# amplification.net
KiCad netlist of a schematic drawn in EAGLE
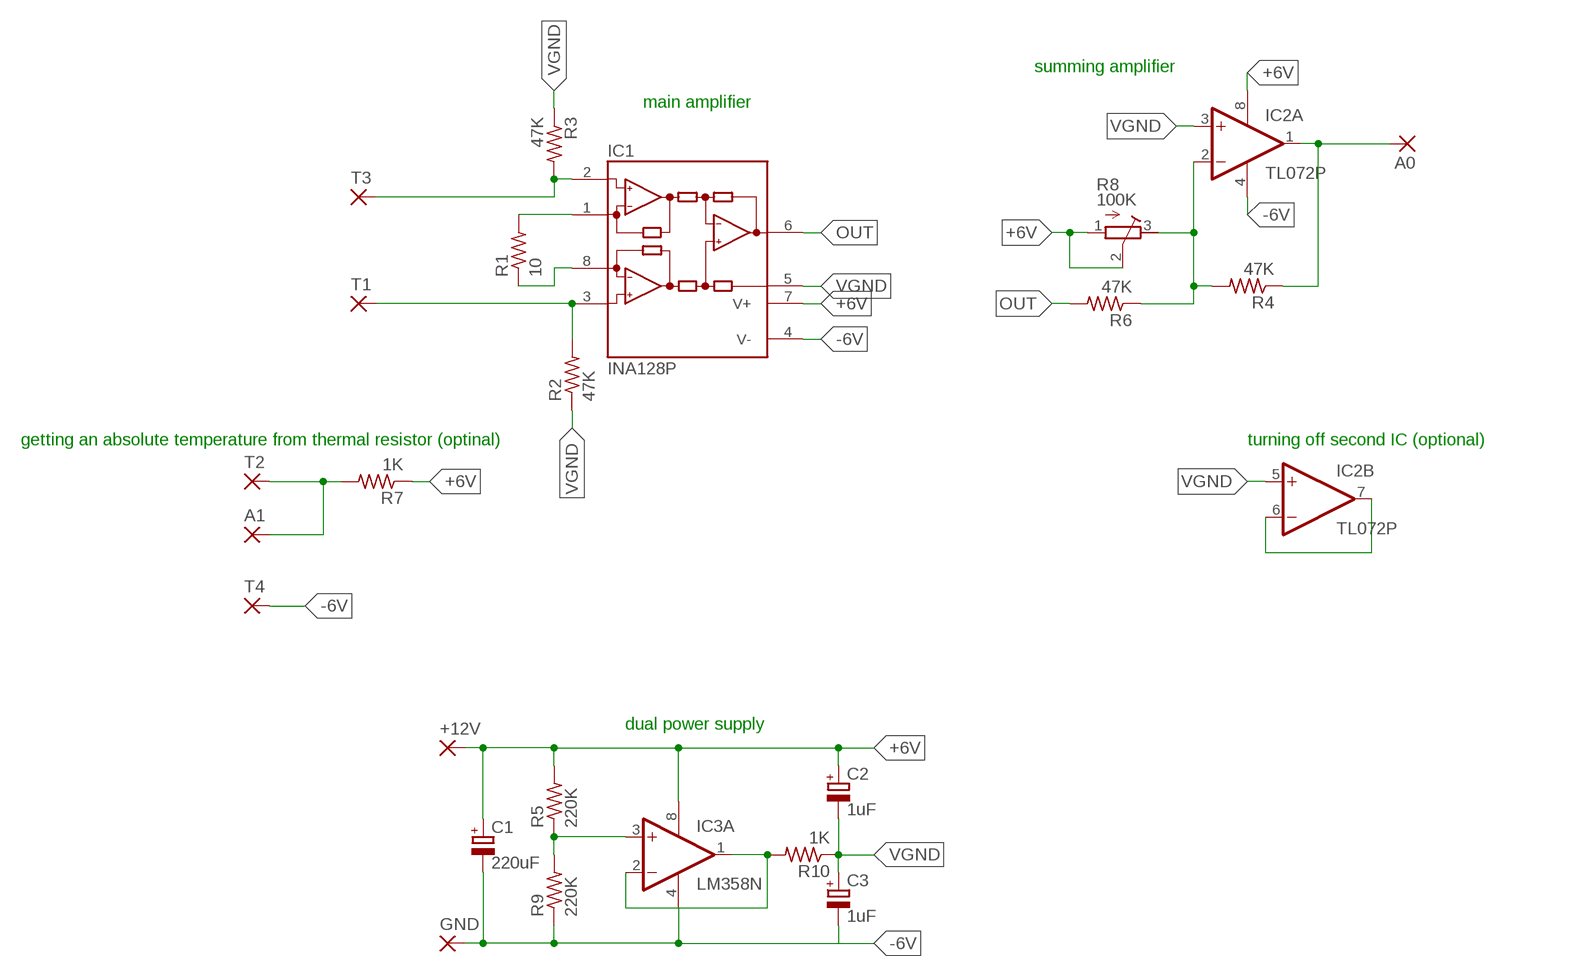
[diagram p0: schematic, sheet 1]

(export (version "E")
  (design (tool "Eeschema 10.0.6"))
  (components
    (comp (ref "+12V")
      (value "2,54/0,8")
      (footprint "eagle-import:2,54_0,8")
      (libsource (lib "eagle-import") (part "2,54/0,8"))
    )
    (comp (ref "A0")
      (value "2,54/0,8")
      (footprint "eagle-import:2,54_0,8")
      (libsource (lib "eagle-import") (part "2,54/0,8"))
    )
    (comp (ref "A1")
      (value "2,54/0,8")
      (footprint "eagle-import:2,54_0,8")
      (libsource (lib "eagle-import") (part "2,54/0,8"))
    )
    (comp (ref "C1")
      (value "220uF")
      (footprint "eagle-import:E2,5-6")
      (libsource (lib "eagle-import") (part "CPOL-EUE2.5-6"))
    )
    (comp (ref "C2")
      (value "1uF")
      (footprint "eagle-import:E2,5-6")
      (libsource (lib "eagle-import") (part "CPOL-EUE2.5-6"))
    )
    (comp (ref "C3")
      (value "1uF")
      (footprint "eagle-import:E2,5-6")
      (libsource (lib "eagle-import") (part "CPOL-EUE2.5-6"))
    )
    (comp (ref "GND")
      (value "2,54/0,8")
      (footprint "eagle-import:2,54_0,8")
      (libsource (lib "eagle-import") (part "2,54/0,8"))
    )
    (comp (ref "IC1")
      (value "INA128P")
      (footprint "eagle-import:DIL08")
      (fields (field (name "MF") "TEXAS INSTRUMENTS"))
      (libsource (lib "eagle-import") (part "INA128P"))
    )
    (comp (ref "IC2")
      (value "TL072P")
      (footprint "eagle-import:DIL08")
      (libsource (lib "eagle-import") (part "TL072P"))
    )
    (comp (ref "IC3")
      (value "LM358N")
      (footprint "eagle-import:DIL08")
      (libsource (lib "eagle-import") (part "LM358N"))
    )
    (comp (ref "R1")
      (value "10")
      (footprint "eagle-import:0207_10")
      (libsource (lib "eagle-import") (part "R-US_0207/10"))
    )
    (comp (ref "R2")
      (value "47K")
      (footprint "eagle-import:0207_10")
      (libsource (lib "eagle-import") (part "R-US_0207/10"))
    )
    (comp (ref "R3")
      (value "47K")
      (footprint "eagle-import:0207_10")
      (libsource (lib "eagle-import") (part "R-US_0207/10"))
    )
    (comp (ref "R4")
      (value "47K")
      (footprint "eagle-import:0207_10")
      (libsource (lib "eagle-import") (part "R-US_0207/10"))
    )
    (comp (ref "R5")
      (value "220K")
      (footprint "eagle-import:0207_10")
      (libsource (lib "eagle-import") (part "R-US_0207/10"))
    )
    (comp (ref "R6")
      (value "47K")
      (footprint "eagle-import:0207_10")
      (libsource (lib "eagle-import") (part "R-US_0207/10"))
    )
    (comp (ref "R7")
      (value "1K")
      (footprint "eagle-import:0207_10")
      (libsource (lib "eagle-import") (part "R-US_0207/10"))
    )
    (comp (ref "R8")
      (value "100K")
      (footprint "eagle-import:RTRIM64W")
      (libsource (lib "eagle-import") (part "R-TRIMM64W"))
    )
    (comp (ref "R9")
      (value "220K")
      (footprint "eagle-import:0207_10")
      (libsource (lib "eagle-import") (part "R-US_0207/10"))
    )
    (comp (ref "R10")
      (value "1K")
      (footprint "eagle-import:0207_10")
      (libsource (lib "eagle-import") (part "R-US_0207/10"))
    )
    (comp (ref "T1")
      (value "2,54/0,8")
      (footprint "eagle-import:2,54_0,8")
      (libsource (lib "eagle-import") (part "2,54/0,8"))
    )
    (comp (ref "T2")
      (value "2,54/0,8")
      (footprint "eagle-import:2,54_0,8")
      (libsource (lib "eagle-import") (part "2,54/0,8"))
    )
    (comp (ref "T3")
      (value "2,54/0,8")
      (footprint "eagle-import:2,54_0,8")
      (libsource (lib "eagle-import") (part "2,54/0,8"))
    )
    (comp (ref "T4")
      (value "2,54/0,8")
      (footprint "eagle-import:2,54_0,8")
      (libsource (lib "eagle-import") (part "2,54/0,8"))
    )
  )
  (nets
    (net (code "1") (name "+6V") (class "Default")
      (node (ref "+12V") (pin "1") (pinfunction "P_1") (pintype "passive"))
      (node (ref "C1") (pin "+") (pinfunction "+_+") (pintype "passive"))
      (node (ref "C2") (pin "+") (pinfunction "+_+") (pintype "passive"))
      (node (ref "IC1") (pin "7") (pinfunction "V+_7") (pintype "power_in"))
      (node (ref "IC2") (pin "8") (pinfunction "V+_8") (pintype "power_in"))
      (node (ref "IC3") (pin "8") (pinfunction "V+_8") (pintype "power_in"))
      (node (ref "R5") (pin "2") (pinfunction "2_2") (pintype "passive"))
      (node (ref "R7") (pin "1") (pinfunction "1_1") (pintype "passive"))
      (node (ref "R8") (pin "1") (pinfunction "A_1") (pintype "passive"))
      (node (ref "R8") (pin "2") (pinfunction "S_2") (pintype "passive"))
    )
    (net (code "2") (name "-6V") (class "Default")
      (node (ref "C1") (pin "-") (pinfunction "-_-") (pintype "passive"))
      (node (ref "C3") (pin "-") (pinfunction "-_-") (pintype "passive"))
      (node (ref "GND") (pin "1") (pinfunction "P_1") (pintype "passive"))
      (node (ref "IC1") (pin "4") (pinfunction "V-_4") (pintype "power_in"))
      (node (ref "IC2") (pin "4") (pinfunction "V-_4") (pintype "power_in"))
      (node (ref "IC3") (pin "4") (pinfunction "V-_4") (pintype "power_in"))
      (node (ref "R9") (pin "1") (pinfunction "1_1") (pintype "passive"))
      (node (ref "T4") (pin "1") (pinfunction "P_1") (pintype "passive"))
    )
    (net (code "3") (name "Net-(A0-P)") (class "Default")
      (node (ref "A0") (pin "1") (pinfunction "P_1") (pintype "passive"))
      (node (ref "IC2") (pin "1") (pinfunction "OUT_1") (pintype "output"))
      (node (ref "R4") (pin "1") (pinfunction "1_1") (pintype "passive"))
    )
    (net (code "4") (name "Net-(A1-P)") (class "Default")
      (node (ref "A1") (pin "1") (pinfunction "P_1") (pintype "passive"))
      (node (ref "R7") (pin "2") (pinfunction "2_2") (pintype "passive"))
      (node (ref "T2") (pin "1") (pinfunction "P_1") (pintype "passive"))
    )
    (net (code "5") (name "Net-(IC1-+IN)") (class "Default")
      (node (ref "IC1") (pin "3") (pinfunction "+IN_3") (pintype "input"))
      (node (ref "R2") (pin "2") (pinfunction "2_2") (pintype "passive"))
      (node (ref "T1") (pin "1") (pinfunction "P_1") (pintype "passive"))
    )
    (net (code "6") (name "Net-(IC1--IN)") (class "Default")
      (node (ref "IC1") (pin "2") (pinfunction "-IN_2") (pintype "input"))
      (node (ref "R3") (pin "2") (pinfunction "2_2") (pintype "passive"))
      (node (ref "T3") (pin "1") (pinfunction "P_1") (pintype "passive"))
    )
    (net (code "7") (name "Net-(IC1-RG-Pad1)") (class "Default")
      (node (ref "IC1") (pin "1") (pinfunction "RG_1") (pintype "passive"))
      (node (ref "R1") (pin "2") (pinfunction "2_2") (pintype "passive"))
    )
    (net (code "8") (name "Net-(IC1-RG-Pad8)") (class "Default")
      (node (ref "IC1") (pin "8") (pinfunction "RG_8") (pintype "passive"))
      (node (ref "R1") (pin "1") (pinfunction "1_1") (pintype "passive"))
    )
    (net (code "9") (name "Net-(IC2A--IN)") (class "Default")
      (node (ref "IC2") (pin "2") (pinfunction "-IN_2") (pintype "input"))
      (node (ref "R4") (pin "2") (pinfunction "2_2") (pintype "passive"))
      (node (ref "R6") (pin "1") (pinfunction "1_1") (pintype "passive"))
      (node (ref "R8") (pin "3") (pinfunction "E_3") (pintype "passive"))
    )
    (net (code "10") (name "Net-(IC2B--IN)") (class "Default")
      (node (ref "IC2") (pin "6") (pinfunction "-IN_6") (pintype "input"))
      (node (ref "IC2") (pin "7") (pinfunction "OUT_7") (pintype "output"))
    )
    (net (code "11") (name "Net-(IC3A-+IN)") (class "Default")
      (node (ref "IC3") (pin "3") (pinfunction "+IN_3") (pintype "input"))
      (node (ref "R5") (pin "1") (pinfunction "1_1") (pintype "passive"))
      (node (ref "R9") (pin "2") (pinfunction "2_2") (pintype "passive"))
    )
    (net (code "12") (name "Net-(IC3A--IN)") (class "Default")
      (node (ref "IC3") (pin "1") (pinfunction "OUT_1") (pintype "output"))
      (node (ref "IC3") (pin "2") (pinfunction "-IN_2") (pintype "input"))
      (node (ref "R10") (pin "2") (pinfunction "2_2") (pintype "passive"))
    )
    (net (code "13") (name "OUT") (class "Default")
      (node (ref "IC1") (pin "6") (pinfunction "OUT_6") (pintype "output"))
      (node (ref "R6") (pin "2") (pinfunction "2_2") (pintype "passive"))
    )
    (net (code "14") (name "VGND") (class "Default")
      (node (ref "C2") (pin "-") (pinfunction "-_-") (pintype "passive"))
      (node (ref "C3") (pin "+") (pinfunction "+_+") (pintype "passive"))
      (node (ref "IC1") (pin "5") (pinfunction "REF_5") (pintype "passive"))
      (node (ref "IC2") (pin "3") (pinfunction "+IN_3") (pintype "input"))
      (node (ref "IC2") (pin "5") (pinfunction "+IN_5") (pintype "input"))
      (node (ref "R10") (pin "1") (pinfunction "1_1") (pintype "passive"))
      (node (ref "R2") (pin "1") (pinfunction "1_1") (pintype "passive"))
      (node (ref "R3") (pin "1") (pinfunction "1_1") (pintype "passive"))
    )
  )
)
